# Communication.net
KiCad netlist of a schematic drawn in Altium Designer
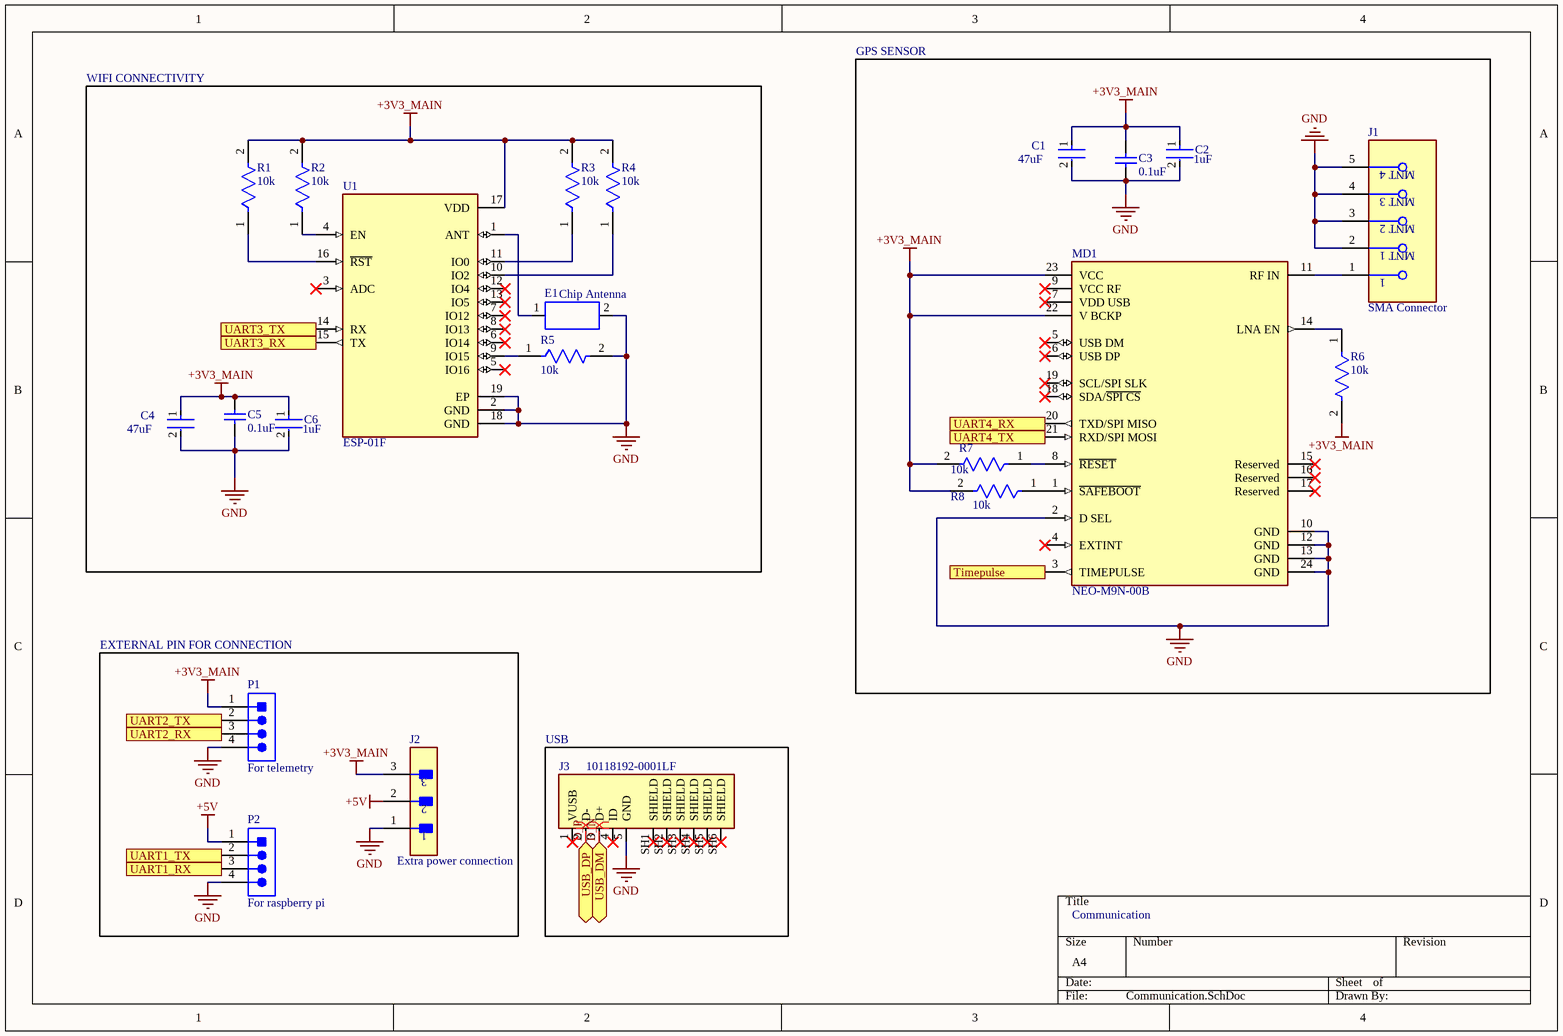
[diagram p0: Communication.SchDoc]

(export (version "E")
  (design (tool "Eeschema 10.0.6"))
  (components
    (comp (ref "C1")
      (value "47uF")
      (footprint "FP-0603-L_1_6_0_2-W_0_8_0-MFG")
      (description "Multilayer Ceramic Capacitor 47uF 4V X6S 20% SMD 0603 T/R")
      (libsource (lib "Altium Content Vault") (part "b4654b650e69147ec39a6b967a45e02"))
    )
    (comp (ref "C2")
      (value "1uF")
      (footprint "FP-GCJ21B-0_3-IPC_B")
      (description "Multilayer Ceramic Capacitors MLCC - SMD/SMT 0805 1uF 10%, 16VDC,  X8L +15/-40%")
      (libsource (lib "Altium Content Vault") (part "02cd4be3c70576c341d710602a673aa"))
    )
    (comp (ref "C3")
      (value "0.1uF")
      (footprint "CAPC1608X87X35ML15T15")
      (fields (field (name "PART NUMBER") "C0603T104K3RCLTU") (field (name "MANUFACTURER") "Kemet"))
      (libsource (lib "Altium Content Vault") (part "CAP"))
    )
    (comp (ref "C4")
      (value "47uF")
      (footprint "FP-0603-L_1_6_0_2-W_0_8_0-MFG")
      (description "Multilayer Ceramic Capacitor 47uF 4V X6S 20% SMD 0603 T/R")
      (libsource (lib "Altium Content Vault") (part "b4654b650e69147ec39a6b967a45e02"))
    )
    (comp (ref "C5")
      (value "0.1uF")
      (footprint "CAPC1608X87X35ML15T15")
      (fields (field (name "PART NUMBER") "C0603T104K3RCLTU") (field (name "MANUFACTURER") "Kemet"))
      (libsource (lib "Altium Content Vault") (part "CAP"))
    )
    (comp (ref "C6")
      (value "1uF")
      (footprint "FP-GCJ21B-0_3-IPC_B")
      (description "Multilayer Ceramic Capacitors MLCC - SMD/SMT 0805 1uF 10%, 16VDC,  X8L +15/-40%")
      (libsource (lib "Altium Content Vault") (part "02cd4be3c70576c341d710602a673aa"))
    )
    (comp (ref "E1")
      (value "Chip Antenna")
      (footprint "TAYO-AH316M-2_M")
      (description "Chip Antenna, 2.4 to 2.5 GHz, -40 to 85 degC, 2-Pin SMD, Pb-Free, Tape and Reel")
      (fields (field (name "MANUFACTURER") "Taiyo Yuden"))
      (libsource (lib "Nauras Shaji") (part "TAYO-RF-ANT-2"))
    )
    (comp (ref "J1")
      (value "SMA Connector")
      (footprint "FP-CON-SMA-EDGE-S-MFG")
      (description "CONN SMA JACK STR EDGE MNT")
      (fields
        (field (name "OCTOPART") "https://octopart.com/con-sma-edge-s-rf+solutions-70967450")
        (field (name "MANUFACTURER PART NUMBER") "CON-SMA-EDGE-S")
      )
      (libsource (lib "Altium Content Vault") (part "a163d97a771fcdd2fd1f1a9264c171f"))
    )
    (comp (ref "J2")
      (value "Extra power connection")
      (footprint "FP-B3B-XH-AM_LF_SN-MFG")
      (description "CONN HEADER VERT 3POS 2.5MM")
      (libsource (lib "Altium Content Vault") (part "0d3f023dd272f625e17a2be33dea85f"))
    )
    (comp (ref "J3")
      (value "10118192-0001LF")
      (footprint "AMPHENOL_10118192-0001LF")
      (description "Micro USB, Input Output Connectors, B TYPE RECEPTACLE with flange")
      (fields (field (name "MF") "Amphenol ICC"))
      (libsource (lib "10118192-0001LF") (part "10118192-0001LF"))
    )
    (comp (ref "MD1")
      (value "NEO-M9N-00B")
      (footprint "FP-NEO-M9N-00B-MFG")
      (description "M9 standard precision module")
      (fields
        (field (name "MANUFACTURER") "u-blox")
        (field (name "OCTOPART") "https://octopart.com/neo-m9n-00b-u-blox-107315722")
      )
      (libsource (lib "Altium Content Vault") (part "6afc83350215ab330c065e89349577f"))
    )
    (comp (ref "P1")
      (value "For telemetry")
      (footprint "JST-B4B-EH-A_V")
      (fields (field (name "MANUFACTURER") "JST"))
      (libsource (lib "Altium Content Vault") (part "CN-1P-M-R4"))
    )
    (comp (ref "P2")
      (value "For raspberry pi")
      (footprint "JST-B4B-EH-A_V")
      (fields (field (name "MANUFACTURER") "JST"))
      (libsource (lib "Altium Content Vault") (part "CN-1P-M-R4"))
    )
    (comp (ref "R1")
      (value "10k")
      (footprint "FP-CRGP0805-IPC_C")
      (description "CRGP 0805 10K 1%")
      (fields (field (name "MANUFACTURER PART NUMBER") "CRGP0805F10K") (field (name "MANUFACTURER") "TE"))
      (libsource (lib "Altium Content Vault") (part "1029c3af85768c4190bb7ad29bc67b5"))
    )
    (comp (ref "R2")
      (value "10k")
      (footprint "FP-CRGP0805-IPC_C")
      (description "CRGP 0805 10K 1%")
      (fields (field (name "MANUFACTURER PART NUMBER") "CRGP0805F10K") (field (name "MANUFACTURER") "TE"))
      (libsource (lib "Altium Content Vault") (part "1029c3af85768c4190bb7ad29bc67b5"))
    )
    (comp (ref "R3")
      (value "10k")
      (footprint "FP-CRGP0805-IPC_C")
      (description "CRGP 0805 10K 1%")
      (fields (field (name "MANUFACTURER PART NUMBER") "CRGP0805F10K") (field (name "MANUFACTURER") "TE"))
      (libsource (lib "Altium Content Vault") (part "1029c3af85768c4190bb7ad29bc67b5"))
    )
    (comp (ref "R4")
      (value "10k")
      (footprint "FP-CRGP0805-IPC_C")
      (description "CRGP 0805 10K 1%")
      (fields (field (name "MANUFACTURER PART NUMBER") "CRGP0805F10K") (field (name "MANUFACTURER") "TE"))
      (libsource (lib "Altium Content Vault") (part "1029c3af85768c4190bb7ad29bc67b5"))
    )
    (comp (ref "R5")
      (value "10k")
      (footprint "FP-CRGP0805-IPC_C")
      (description "CRGP 0805 10K 1%")
      (fields (field (name "MANUFACTURER PART NUMBER") "CRGP0805F10K") (field (name "MANUFACTURER") "TE"))
      (libsource (lib "Altium Content Vault") (part "1029c3af85768c4190bb7ad29bc67b5"))
    )
    (comp (ref "R6")
      (value "10k")
      (footprint "FP-CRGP0805-IPC_C")
      (description "CRGP 0805 10K 1%")
      (fields (field (name "MANUFACTURER PART NUMBER") "CRGP0805F10K") (field (name "MANUFACTURER") "TE"))
      (libsource (lib "Altium Content Vault") (part "1029c3af85768c4190bb7ad29bc67b5"))
    )
    (comp (ref "R7")
      (value "10k")
      (footprint "FP-CRGP0805-IPC_C")
      (description "CRGP 0805 10K 1%")
      (fields (field (name "MANUFACTURER PART NUMBER") "CRGP0805F10K") (field (name "MANUFACTURER") "TE"))
      (libsource (lib "Altium Content Vault") (part "1029c3af85768c4190bb7ad29bc67b5"))
    )
    (comp (ref "R8")
      (value "10k")
      (footprint "FP-CRGP0805-IPC_C")
      (description "CRGP 0805 10K 1%")
      (fields (field (name "MANUFACTURER PART NUMBER") "CRGP0805F10K") (field (name "MANUFACTURER") "TE"))
      (libsource (lib "Altium Content Vault") (part "1029c3af85768c4190bb7ad29bc67b5"))
    )
    (comp (ref "U1")
      (value "ESP-01F")
      (footprint "MODULE_ESP-01F")
      (description "802.11b/g/n Wi-Fi SOC module")
      (fields (field (name "MF") "AI-Thinker"))
      (libsource (lib "ESP-01F") (part "ESP-01F"))
    )
  )
  (nets
    (net (code "1") (name "+3V3_MAIN") (class "Default")
      (node (ref "C1") (pin "1") (pinfunction "1_1") (pintype "passive"))
      (node (ref "C2") (pin "1") (pinfunction "1_1") (pintype "passive"))
      (node (ref "C3") (pin "2") (pinfunction "2_2") (pintype "passive"))
      (node (ref "C4") (pin "1") (pinfunction "1_1") (pintype "passive"))
      (node (ref "C5") (pin "2") (pinfunction "2_2") (pintype "passive"))
      (node (ref "C6") (pin "1") (pinfunction "1_1") (pintype "passive"))
      (node (ref "J2") (pin "3") (pinfunction "3_3") (pintype "passive"))
      (node (ref "MD1") (pin "22") (pinfunction "V_BCKP_22") (pintype "power_in"))
      (node (ref "MD1") (pin "23") (pinfunction "VCC_23") (pintype "power_in"))
      (node (ref "P1") (pin "1") (pinfunction "1_1") (pintype "passive"))
      (node (ref "R1") (pin "2") (pinfunction "2_2") (pintype "passive"))
      (node (ref "R2") (pin "2") (pinfunction "2_2") (pintype "passive"))
      (node (ref "R3") (pin "2") (pinfunction "2_2") (pintype "passive"))
      (node (ref "R4") (pin "2") (pinfunction "2_2") (pintype "passive"))
      (node (ref "R6") (pin "2") (pinfunction "2_2") (pintype "passive"))
      (node (ref "R7") (pin "2") (pinfunction "2_2") (pintype "passive"))
      (node (ref "R8") (pin "2") (pinfunction "2_2") (pintype "passive"))
      (node (ref "U1") (pin "17") (pinfunction "VDD_17") (pintype "power_in"))
    )
    (net (code "2") (name "+5V") (class "Default")
      (node (ref "J2") (pin "2") (pinfunction "2_2") (pintype "passive"))
      (node (ref "P2") (pin "1") (pinfunction "1_1") (pintype "passive"))
    )
    (net (code "3") (name "/D_N") (class "Default")
      (node (ref "J3") (pin "3") (pinfunction "D+_3") (pintype "passive"))
    )
    (net (code "4") (name "/D_P") (class "Default")
      (node (ref "J3") (pin "2") (pinfunction "D-_2") (pintype "passive"))
    )
    (net (code "5") (name "/Timepulse") (class "Default")
      (node (ref "MD1") (pin "3") (pinfunction "TIMEPULSE_3") (pintype "output"))
    )
    (net (code "6") (name "/UART1_RX") (class "Default")
      (node (ref "P2") (pin "3") (pinfunction "3_3") (pintype "passive"))
    )
    (net (code "7") (name "/UART1_TX") (class "Default")
      (node (ref "P2") (pin "2") (pinfunction "2_2") (pintype "passive"))
    )
    (net (code "8") (name "/UART2_RX") (class "Default")
      (node (ref "P1") (pin "3") (pinfunction "3_3") (pintype "passive"))
    )
    (net (code "9") (name "/UART2_TX") (class "Default")
      (node (ref "P1") (pin "2") (pinfunction "2_2") (pintype "passive"))
    )
    (net (code "10") (name "/UART3_RX") (class "Default")
      (node (ref "U1") (pin "15") (pinfunction "TX_15") (pintype "output"))
    )
    (net (code "11") (name "/UART3_TX") (class "Default")
      (node (ref "U1") (pin "14") (pinfunction "RX_14") (pintype "input"))
    )
    (net (code "12") (name "/UART4_RX") (class "Default")
      (node (ref "MD1") (pin "20") (pinfunction "TXD/SPI_MISO_20") (pintype "output"))
    )
    (net (code "13") (name "/UART4_TX") (class "Default")
      (node (ref "MD1") (pin "21") (pinfunction "RXD/SPI_MOSI_21") (pintype "input"))
    )
    (net (code "14") (name "GND") (class "Default")
      (node (ref "C1") (pin "2") (pinfunction "2_2") (pintype "passive"))
      (node (ref "C2") (pin "2") (pinfunction "2_2") (pintype "passive"))
      (node (ref "C3") (pin "1") (pinfunction "1_1") (pintype "passive"))
      (node (ref "C4") (pin "2") (pinfunction "2_2") (pintype "passive"))
      (node (ref "C5") (pin "1") (pinfunction "1_1") (pintype "passive"))
      (node (ref "C6") (pin "2") (pinfunction "2_2") (pintype "passive"))
      (node (ref "E1") (pin "2") (pinfunction "2_2") (pintype "passive"))
      (node (ref "J1") (pin "2") (pinfunction "MNT_1_2") (pintype "passive"))
      (node (ref "J1") (pin "3") (pinfunction "MNT_2_3") (pintype "passive"))
      (node (ref "J1") (pin "4") (pinfunction "MNT_3_4") (pintype "passive"))
      (node (ref "J1") (pin "5") (pinfunction "MNT_4_5") (pintype "passive"))
      (node (ref "J2") (pin "1") (pinfunction "1_1") (pintype "passive"))
      (node (ref "J3") (pin "5") (pinfunction "GND_5") (pintype "passive"))
      (node (ref "MD1") (pin "10") (pinfunction "GND_10") (pintype "power_in"))
      (node (ref "MD1") (pin "12") (pinfunction "GND_12") (pintype "power_in"))
      (node (ref "MD1") (pin "13") (pinfunction "GND_13") (pintype "power_in"))
      (node (ref "MD1") (pin "2") (pinfunction "D_SEL_2") (pintype "input"))
      (node (ref "MD1") (pin "24") (pinfunction "GND_24") (pintype "power_in"))
      (node (ref "P1") (pin "4") (pinfunction "4_4") (pintype "passive"))
      (node (ref "P2") (pin "4") (pinfunction "4_4") (pintype "passive"))
      (node (ref "R5") (pin "2") (pinfunction "2_2") (pintype "passive"))
      (node (ref "U1") (pin "18") (pinfunction "GND_18") (pintype "power_in"))
      (node (ref "U1") (pin "19") (pinfunction "EP_19") (pintype "passive"))
      (node (ref "U1") (pin "2") (pinfunction "GND_2") (pintype "power_in"))
    )
    (net (code "15") (name "Net-(MD1-LNA_EN)") (class "Default")
      (node (ref "MD1") (pin "14") (pinfunction "LNA_EN_14") (pintype "output"))
      (node (ref "R6") (pin "1") (pinfunction "1_1") (pintype "passive"))
    )
    (net (code "16") (name "Net-(MD1-RF_IN)") (class "Default")
      (node (ref "J1") (pin "1") (pinfunction "1_1") (pintype "passive"))
      (node (ref "MD1") (pin "11") (pinfunction "RF_IN_11") (pintype "passive"))
    )
    (net (code "17") (name "Net-(MD1-~{RESET})") (class "Default")
      (node (ref "MD1") (pin "8") (pinfunction "~{RESET}_8") (pintype "input"))
      (node (ref "R7") (pin "1") (pinfunction "1_1") (pintype "passive"))
    )
    (net (code "18") (name "Net-(MD1-~{SAFEBOOT})") (class "Default")
      (node (ref "MD1") (pin "1") (pinfunction "~{SAFEBOOT}_1") (pintype "input"))
      (node (ref "R8") (pin "1") (pinfunction "1_1") (pintype "passive"))
    )
    (net (code "19") (name "Net-(U1-ANT)") (class "Default")
      (node (ref "E1") (pin "1") (pinfunction "1_1") (pintype "passive"))
      (node (ref "U1") (pin "1") (pinfunction "ANT_1") (pintype "bidirectional"))
    )
    (net (code "20") (name "Net-(U1-EN)") (class "Default")
      (node (ref "R2") (pin "1") (pinfunction "1_1") (pintype "passive"))
      (node (ref "U1") (pin "4") (pinfunction "EN_4") (pintype "input"))
    )
    (net (code "21") (name "Net-(U1-IO0)") (class "Default")
      (node (ref "R3") (pin "1") (pinfunction "1_1") (pintype "passive"))
      (node (ref "U1") (pin "11") (pinfunction "IO0_11") (pintype "bidirectional"))
    )
    (net (code "22") (name "Net-(U1-IO2)") (class "Default")
      (node (ref "R4") (pin "1") (pinfunction "1_1") (pintype "passive"))
      (node (ref "U1") (pin "10") (pinfunction "IO2_10") (pintype "bidirectional"))
    )
    (net (code "23") (name "Net-(U1-IO15)") (class "Default")
      (node (ref "R5") (pin "1") (pinfunction "1_1") (pintype "passive"))
      (node (ref "U1") (pin "9") (pinfunction "IO15_9") (pintype "bidirectional"))
    )
    (net (code "24") (name "Net-(U1-~{RST})") (class "Default")
      (node (ref "R1") (pin "1") (pinfunction "1_1") (pintype "passive"))
      (node (ref "U1") (pin "16") (pinfunction "~{RST}_16") (pintype "input"))
    )
    (net (code "25") (name "unconnected-(J3-ID-Pad4)") (class "Default")
      (node (ref "J3") (pin "4") (pinfunction "ID_4") (pintype "passive+no_connect"))
    )
    (net (code "26") (name "unconnected-(J3-SHIELD-PadSH1)") (class "Default")
      (node (ref "J3") (pin "SH1") (pinfunction "SHIELD_SH1") (pintype "passive+no_connect"))
    )
    (net (code "27") (name "unconnected-(J3-SHIELD-PadSH2)") (class "Default")
      (node (ref "J3") (pin "SH2") (pinfunction "SHIELD_SH2") (pintype "passive+no_connect"))
    )
    (net (code "28") (name "unconnected-(J3-SHIELD-PadSH3)") (class "Default")
      (node (ref "J3") (pin "SH3") (pinfunction "SHIELD_SH3") (pintype "passive+no_connect"))
    )
    (net (code "29") (name "unconnected-(J3-SHIELD-PadSH4)") (class "Default")
      (node (ref "J3") (pin "SH4") (pinfunction "SHIELD_SH4") (pintype "passive+no_connect"))
    )
    (net (code "30") (name "unconnected-(J3-SHIELD-PadSH5)") (class "Default")
      (node (ref "J3") (pin "SH5") (pinfunction "SHIELD_SH5") (pintype "passive+no_connect"))
    )
    (net (code "31") (name "unconnected-(J3-SHIELD-PadSH6)") (class "Default")
      (node (ref "J3") (pin "SH6") (pinfunction "SHIELD_SH6") (pintype "passive+no_connect"))
    )
    (net (code "32") (name "unconnected-(J3-VUSB-Pad1)") (class "Default")
      (node (ref "J3") (pin "1") (pinfunction "VUSB_1") (pintype "passive+no_connect"))
    )
    (net (code "33") (name "unconnected-(MD1-EXTINT-Pad4)") (class "Default")
      (node (ref "MD1") (pin "4") (pinfunction "EXTINT_4") (pintype "input+no_connect"))
    )
    (net (code "34") (name "unconnected-(MD1-Reserved-Pad15)") (class "Default")
      (node (ref "MD1") (pin "15") (pinfunction "Reserved_15") (pintype "passive+no_connect"))
    )
    (net (code "35") (name "unconnected-(MD1-Reserved-Pad16)") (class "Default")
      (node (ref "MD1") (pin "16") (pinfunction "Reserved_16") (pintype "passive+no_connect"))
    )
    (net (code "36") (name "unconnected-(MD1-Reserved-Pad17)") (class "Default")
      (node (ref "MD1") (pin "17") (pinfunction "Reserved_17") (pintype "passive+no_connect"))
    )
    (net (code "37") (name "unconnected-(MD1-SCL{slash}SPI_SLK-Pad19)") (class "Default")
      (node (ref "MD1") (pin "19") (pinfunction "SCL/SPI_SLK_19") (pintype "bidirectional+no_connect"))
    )
    (net (code "38") (name "unconnected-(MD1-SDA{slash}~{SPI_CS}-Pad18)") (class "Default")
      (node (ref "MD1") (pin "18") (pinfunction "SDA/~{SPI_CS}_18") (pintype "bidirectional+no_connect"))
    )
    (net (code "39") (name "unconnected-(MD1-USB_DM-Pad5)") (class "Default")
      (node (ref "MD1") (pin "5") (pinfunction "USB_DM_5") (pintype "bidirectional+no_connect"))
    )
    (net (code "40") (name "unconnected-(MD1-USB_DP-Pad6)") (class "Default")
      (node (ref "MD1") (pin "6") (pinfunction "USB_DP_6") (pintype "bidirectional+no_connect"))
    )
    (net (code "41") (name "unconnected-(MD1-VCC_RF-Pad9)") (class "Default")
      (node (ref "MD1") (pin "9") (pinfunction "VCC_RF_9") (pintype "power_in+no_connect"))
    )
    (net (code "42") (name "unconnected-(MD1-VDD_USB-Pad7)") (class "Default")
      (node (ref "MD1") (pin "7") (pinfunction "VDD_USB_7") (pintype "power_in+no_connect"))
    )
    (net (code "43") (name "unconnected-(U1-ADC-Pad3)") (class "Default")
      (node (ref "U1") (pin "3") (pinfunction "ADC_3") (pintype "input+no_connect"))
    )
    (net (code "44") (name "unconnected-(U1-IO4-Pad12)") (class "Default")
      (node (ref "U1") (pin "12") (pinfunction "IO4_12") (pintype "bidirectional+no_connect"))
    )
    (net (code "45") (name "unconnected-(U1-IO5-Pad13)") (class "Default")
      (node (ref "U1") (pin "13") (pinfunction "IO5_13") (pintype "bidirectional+no_connect"))
    )
    (net (code "46") (name "unconnected-(U1-IO12-Pad7)") (class "Default")
      (node (ref "U1") (pin "7") (pinfunction "IO12_7") (pintype "bidirectional+no_connect"))
    )
    (net (code "47") (name "unconnected-(U1-IO13-Pad8)") (class "Default")
      (node (ref "U1") (pin "8") (pinfunction "IO13_8") (pintype "bidirectional+no_connect"))
    )
    (net (code "48") (name "unconnected-(U1-IO14-Pad6)") (class "Default")
      (node (ref "U1") (pin "6") (pinfunction "IO14_6") (pintype "bidirectional+no_connect"))
    )
    (net (code "49") (name "unconnected-(U1-IO16-Pad5)") (class "Default")
      (node (ref "U1") (pin "5") (pinfunction "IO16_5") (pintype "bidirectional+no_connect"))
    )
  )
)
